# CAN.net
KiCad netlist of a schematic drawn in Altium Designer
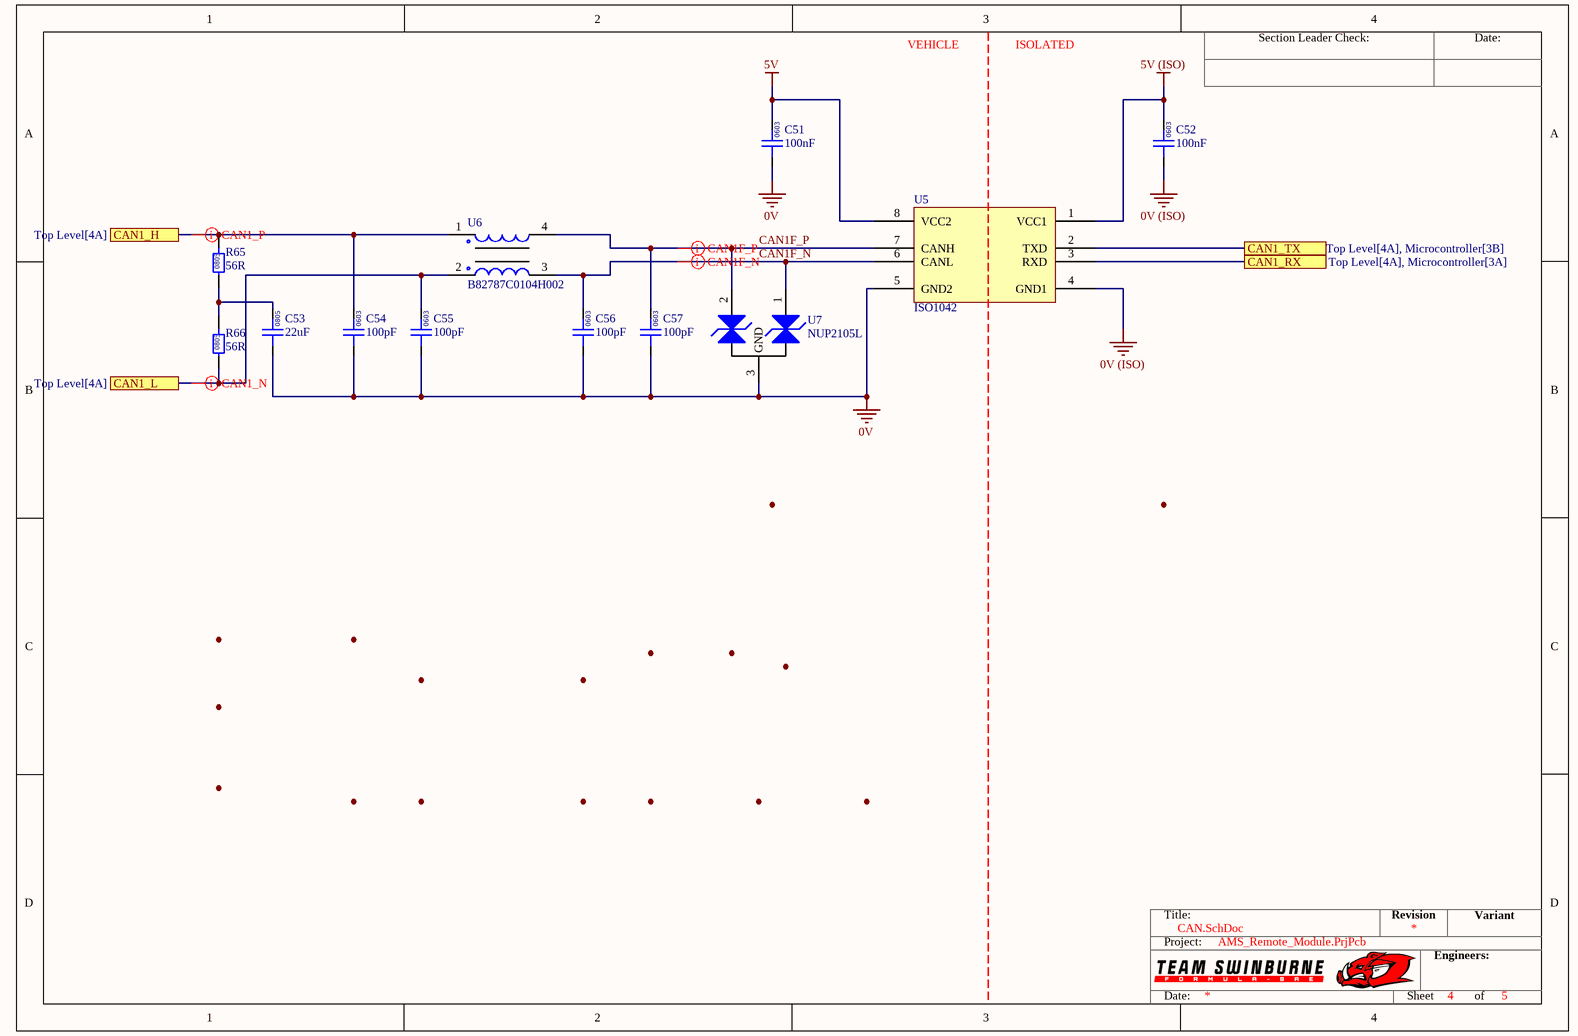
[diagram p0: CAN.SchDoc]

(export (version "E")
  (design (tool "Eeschema 10.0.6"))
  (components
    (comp (ref "C51")
      (value "100nF")
      (footprint "0603")
      (fields
        (field (name "PART NUMBER") "GCM188L81H104KA57D")
        (field (name "MANUFACTURER") "muRata")
        (field (name "TOLERANCE") "±10%")
      )
      (libsource (lib "ts_standard_library") (part "Capacitor 0603"))
    )
    (comp (ref "C52")
      (value "100nF")
      (footprint "0603")
      (fields
        (field (name "PART NUMBER") "GCM188L81H104KA57D")
        (field (name "MANUFACTURER") "muRata")
        (field (name "TOLERANCE") "±10%")
      )
      (libsource (lib "ts_standard_library") (part "Capacitor 0603"))
    )
    (comp (ref "C53")
      (value "22uF")
      (footprint "0805")
      (fields
        (field (name "PART NUMBER") "GRM21BR61A226ME51L")
        (field (name "MANUFACTURER") "muRata")
        (field (name "TOLERANCE") "20%")
      )
      (libsource (lib "ts_standard_library") (part "Capacitor 0805"))
    )
    (comp (ref "C54")
      (value "100pF")
      (footprint "0603")
      (fields
        (field (name "PART NUMBER") "GRM1885C1H101JA01D")
        (field (name "MANUFACTURER") "Murata Electronics")
        (field (name "TOLERANCE") "±5%")
      )
      (libsource (lib "ts_standard_library") (part "Capacitor 0603"))
    )
    (comp (ref "C55")
      (value "100pF")
      (footprint "0603")
      (fields
        (field (name "PART NUMBER") "GRM1885C1H101JA01D")
        (field (name "MANUFACTURER") "Murata Electronics")
        (field (name "TOLERANCE") "±5%")
      )
      (libsource (lib "ts_standard_library") (part "Capacitor 0603"))
    )
    (comp (ref "C56")
      (value "100pF")
      (footprint "0603")
      (fields
        (field (name "PART NUMBER") "GRM1885C1H101JA01D")
        (field (name "MANUFACTURER") "Murata Electronics")
        (field (name "TOLERANCE") "±5%")
      )
      (libsource (lib "ts_standard_library") (part "Capacitor 0603"))
    )
    (comp (ref "C57")
      (value "100pF")
      (footprint "0603")
      (fields
        (field (name "PART NUMBER") "GRM1885C1H101JA01D")
        (field (name "MANUFACTURER") "Murata Electronics")
        (field (name "TOLERANCE") "±5%")
      )
      (libsource (lib "ts_standard_library") (part "Capacitor 0603"))
    )
    (comp (ref "R65")
      (value "56R")
      (footprint "0805")
      (fields
        (field (name "PART NUMBER") "RC0805FR0756RL")
        (field (name "MANUFACTURER") "YAGEO")
        (field (name "TOLERANCE") "0.01")
      )
      (libsource (lib "ts_standard_library") (part "Resistor 0805"))
    )
    (comp (ref "R66")
      (value "56R")
      (footprint "0805")
      (fields
        (field (name "PART NUMBER") "RC0805FR0756RL")
        (field (name "MANUFACTURER") "YAGEO")
        (field (name "TOLERANCE") "0.01")
      )
      (libsource (lib "ts_standard_library") (part "Resistor 0805"))
    )
    (comp (ref "U5")
      (value "ISO1042")
      (footprint "TI-SOIC-8")
      (description "IC CAN TRANSCEIVER 1/1 8SOIC")
      (fields
        (field (name "MANUFACTURER") "Texas Instruments")
        (field (name "DIGIKEY PART NUMBER") "296-ISO1042BQDWVQ1-ND")
      )
      (libsource (lib "ts_standard_library") (part "ISO1042"))
    )
    (comp (ref "U6")
      (value "B82787C0104H002")
      (footprint "TDK 4-PC Pad")
      (fields
        (field (name "MANUFACTURER") "EPCOS (TDK)")
        (field (name "DIGIKEY PART NUMBER") "495-4598-1-ND")
      )
      (libsource (lib "ts_standard_library") (part "B82787C0104H002"))
    )
    (comp (ref "U7")
      (value "NUP2105L")
      (footprint "ON SOT-23")
      (description "Dual Line CAN Bus Protector")
      (fields
        (field (name "MANUFACTURER") "ON Semiconductor")
        (field (name "DIGIKEY PART NUMBER") "NUP2105LT1GOSCT-ND")
      )
      (libsource (lib "ts_standard_library") (part "NUP2105L"))
    )
  )
  (nets
    (net (code "1") (name "/CAN1F_N") (class "Default")
      (node (ref "C56") (pin "2") (pinfunction "2_2") (pintype "passive"))
      (node (ref "U5") (pin "6") (pinfunction "CANL_6") (pintype "passive"))
      (node (ref "U6") (pin "3") (pinfunction "3_3") (pintype "passive"))
      (node (ref "U7") (pin "1") (pinfunction "CAN_H_1") (pintype "passive"))
    )
    (net (code "2") (name "/CAN1F_P") (class "Default")
      (node (ref "C57") (pin "2") (pinfunction "2_2") (pintype "passive"))
      (node (ref "U5") (pin "7") (pinfunction "CANH_7") (pintype "passive"))
      (node (ref "U6") (pin "4") (pinfunction "4_4") (pintype "passive"))
      (node (ref "U7") (pin "2") (pinfunction "CAN_L_2") (pintype "passive"))
    )
    (net (code "3") (name "/CAN1_H") (class "Default")
      (node (ref "C54") (pin "2") (pinfunction "2_2") (pintype "passive"))
      (node (ref "R65") (pin "2") (pinfunction "2_2") (pintype "passive"))
      (node (ref "U6") (pin "1") (pinfunction "1_1") (pintype "passive"))
    )
    (net (code "4") (name "/CAN1_L") (class "Default")
      (node (ref "C55") (pin "2") (pinfunction "2_2") (pintype "passive"))
      (node (ref "R66") (pin "1") (pinfunction "1_1") (pintype "passive"))
      (node (ref "U6") (pin "2") (pinfunction "2_2") (pintype "passive"))
    )
    (net (code "5") (name "/CAN1_RX") (class "Default")
      (node (ref "U5") (pin "3") (pinfunction "RXD_3") (pintype "passive"))
    )
    (net (code "6") (name "/CAN1_TX") (class "Default")
      (node (ref "U5") (pin "2") (pinfunction "TXD_2") (pintype "passive"))
    )
    (net (code "7") (name "0V") (class "Default")
      (node (ref "C51") (pin "1") (pinfunction "1_1") (pintype "passive"))
      (node (ref "C53") (pin "1") (pinfunction "1_1") (pintype "passive"))
      (node (ref "C54") (pin "1") (pinfunction "1_1") (pintype "passive"))
      (node (ref "C55") (pin "1") (pinfunction "1_1") (pintype "passive"))
      (node (ref "C56") (pin "1") (pinfunction "1_1") (pintype "passive"))
      (node (ref "C57") (pin "1") (pinfunction "1_1") (pintype "passive"))
      (node (ref "U5") (pin "5") (pinfunction "GND2_5") (pintype "passive"))
      (node (ref "U7") (pin "3") (pinfunction "GND_3") (pintype "passive"))
    )
    (net (code "8") (name "0V (ISO)") (class "Default")
      (node (ref "C52") (pin "1") (pinfunction "1_1") (pintype "passive"))
      (node (ref "U5") (pin "4") (pinfunction "GND1_4") (pintype "passive"))
    )
    (net (code "9") (name "5V") (class "Default")
      (node (ref "C51") (pin "2") (pinfunction "2_2") (pintype "passive"))
      (node (ref "U5") (pin "8") (pinfunction "VCC2_8") (pintype "passive"))
    )
    (net (code "10") (name "5V (ISO)") (class "Default")
      (node (ref "C52") (pin "2") (pinfunction "2_2") (pintype "passive"))
      (node (ref "U5") (pin "1") (pinfunction "VCC1_1") (pintype "passive"))
    )
    (net (code "11") (name "Net-(C53-Pad2)") (class "Default")
      (node (ref "C53") (pin "2") (pinfunction "2_2") (pintype "passive"))
      (node (ref "R65") (pin "1") (pinfunction "1_1") (pintype "passive"))
      (node (ref "R66") (pin "2") (pinfunction "2_2") (pintype "passive"))
    )
  )
)
